# mainSchem.net
KiCad netlist of a schematic drawn in Altium Designer
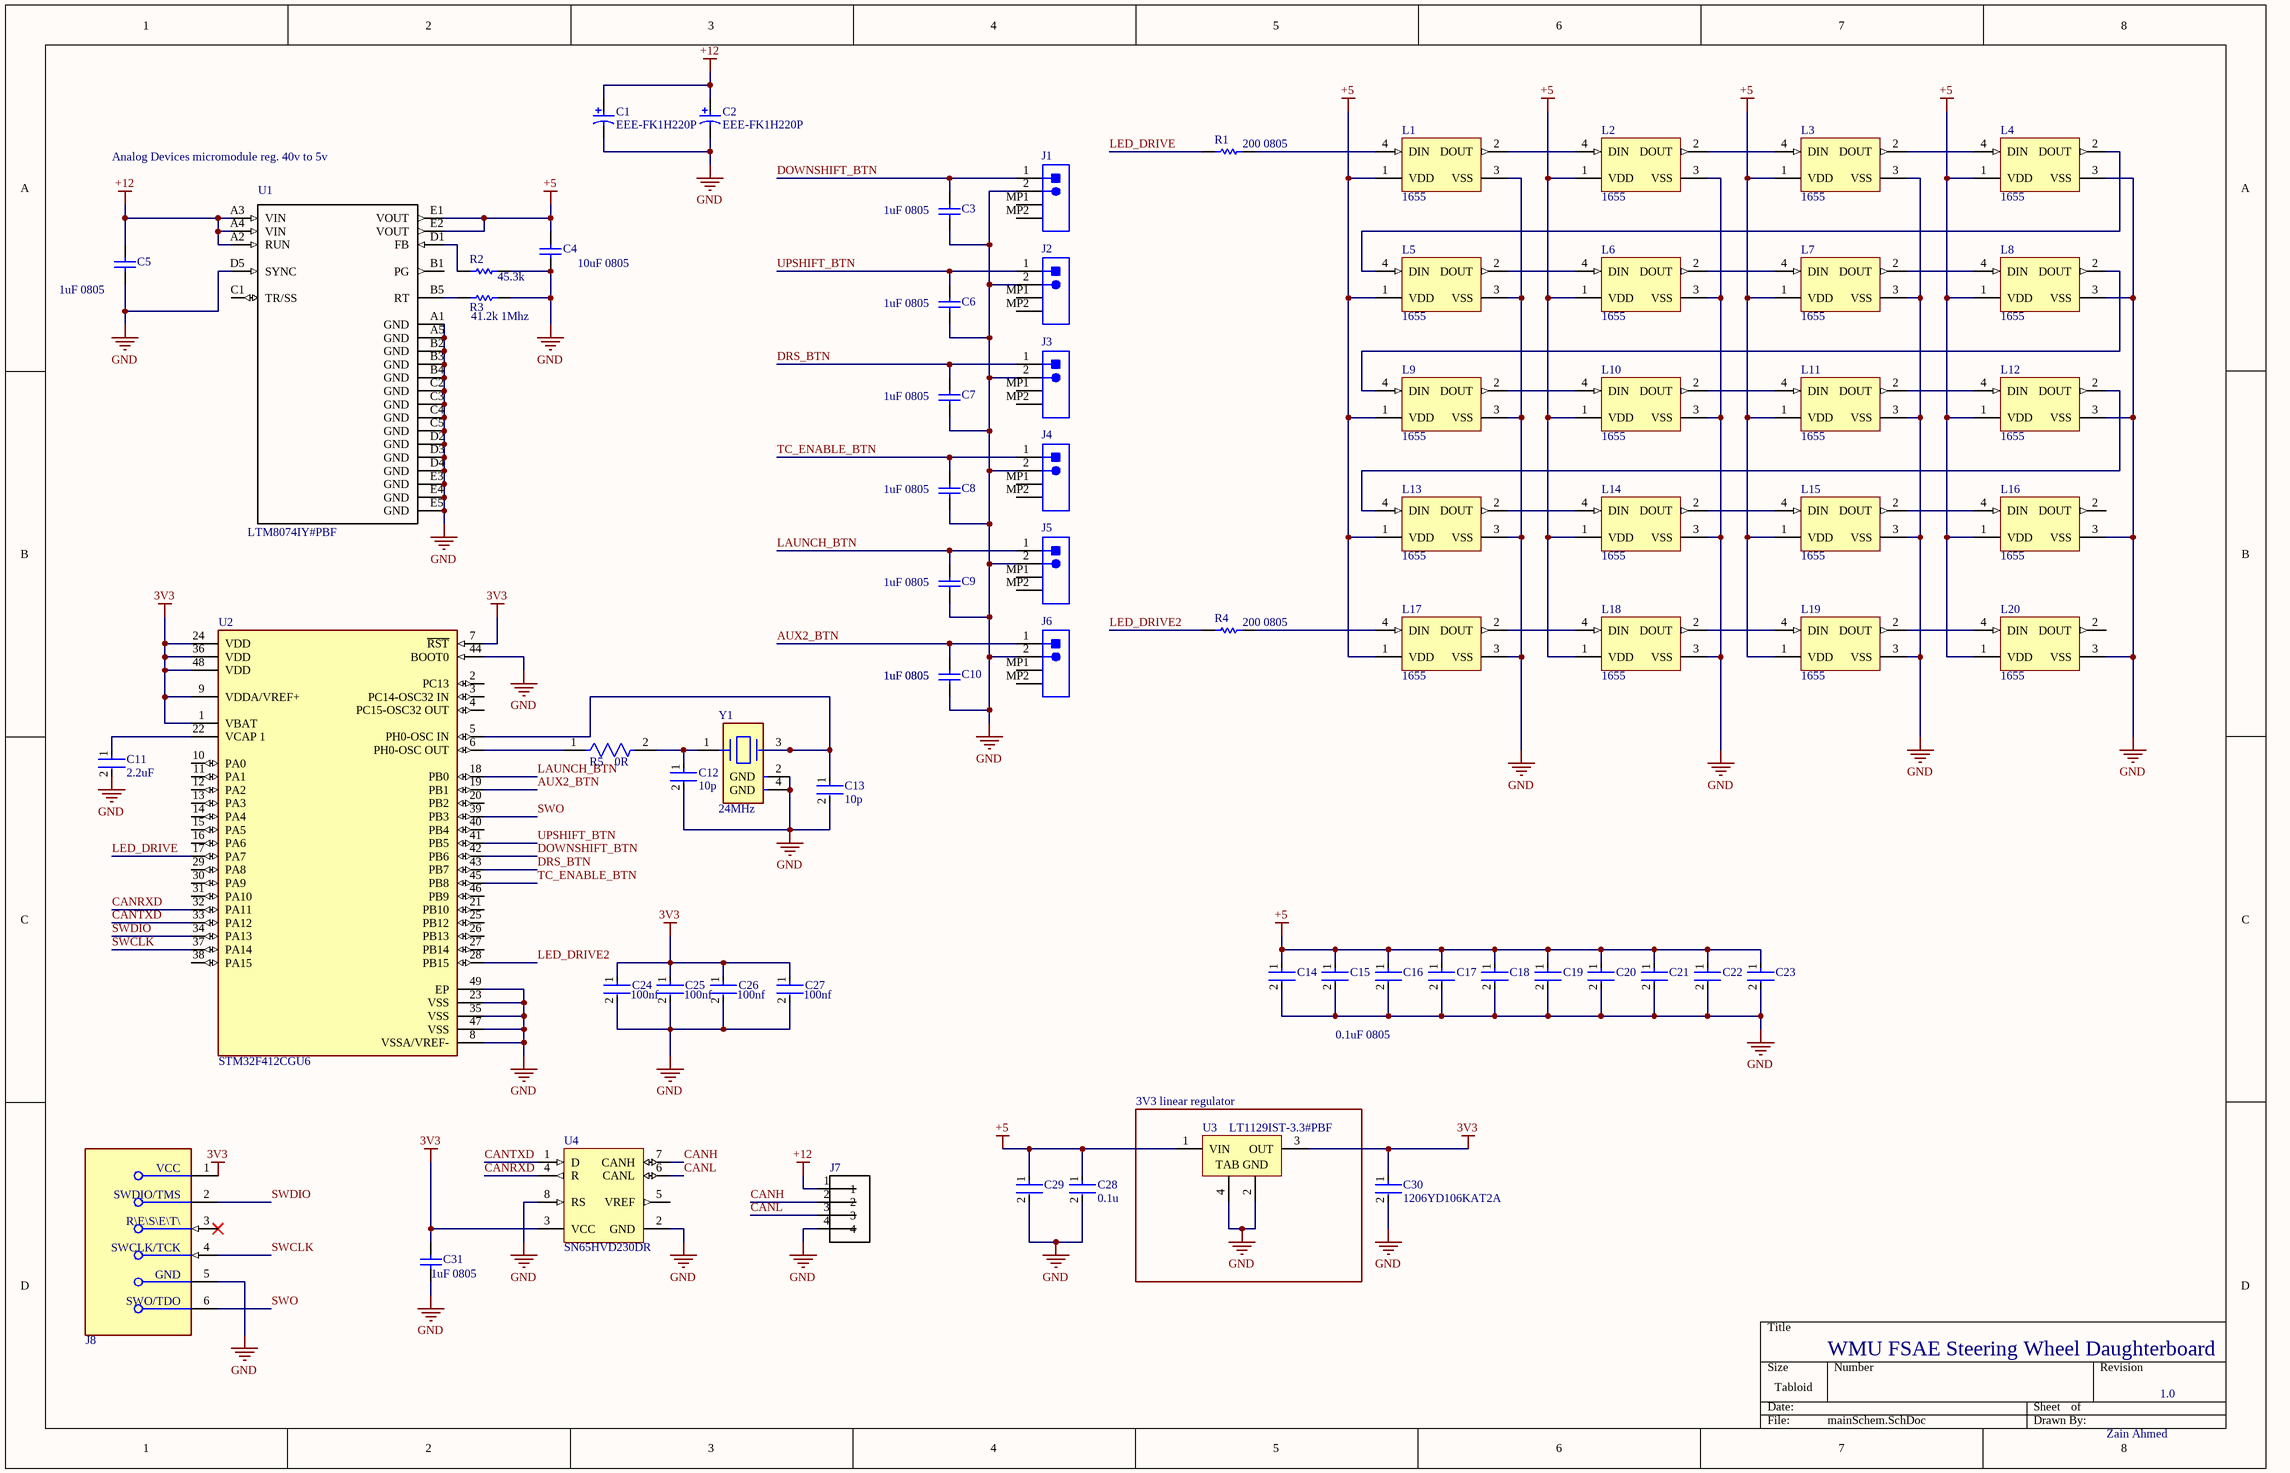
[diagram p0: mainSchem.SchDoc]

(export (version "E")
  (design (tool "Eeschema 10.0.6"))
  (components
    (comp (ref "C1")
      (value "EEE-FK1H220P")
      (footprint "PNSC-EEE-FK1H220P_L")
      (description "Cap Aluminum Lytic, 22 uF, +/- 20%, 6.3 to 100 V, -55 to 105 degC, 2-Pin SMD, RoHS, Tape and Reel")
      (fields (field (name "MANUFACTURER") "Panasonic"))
      (libsource (lib "Altium Content Vault") (part "CAP-P-2"))
    )
    (comp (ref "C2")
      (value "EEE-FK1H220P")
      (footprint "PNSC-EEE-FK1H220P_L")
      (description "Cap Aluminum Lytic, 22 uF, +/- 20%, 6.3 to 100 V, -55 to 105 degC, 2-Pin SMD, RoHS, Tape and Reel")
      (fields (field (name "MANUFACTURER") "Panasonic"))
      (libsource (lib "Altium Content Vault") (part "CAP-P-2"))
    )
    (comp (ref "C3")
      (value "GRM216R61E105KA12D")
      (footprint "CAPC2013X70X45NL10T25")
      (fields (field (name "MANUFACTURER") "Murata"))
      (libsource (lib "Altium Content Vault") (part "CAP"))
    )
    (comp (ref "C4")
      (value "GRM21BR61C106KE15L")
      (footprint "CAPC2013X135X50LL10T20")
      (fields (field (name "MANUFACTURER") "Murata"))
      (libsource (lib "Altium Content Vault") (part "CAP"))
    )
    (comp (ref "C5")
      (value "GRM216R61E105KA12D")
      (footprint "CAPC2013X70X45NL10T25")
      (fields (field (name "MANUFACTURER") "Murata"))
      (libsource (lib "Altium Content Vault") (part "CAP"))
    )
    (comp (ref "C6")
      (value "GRM216R61E105KA12D")
      (footprint "CAPC2013X70X45NL10T25")
      (fields (field (name "MANUFACTURER") "Murata"))
      (libsource (lib "Altium Content Vault") (part "CAP"))
    )
    (comp (ref "C7")
      (value "GRM216R61E105KA12D")
      (footprint "CAPC2013X70X45NL10T25")
      (fields (field (name "MANUFACTURER") "Murata"))
      (libsource (lib "Altium Content Vault") (part "CAP"))
    )
    (comp (ref "C8")
      (value "GRM216R61E105KA12D")
      (footprint "CAPC2013X70X45NL10T25")
      (fields (field (name "MANUFACTURER") "Murata"))
      (libsource (lib "Altium Content Vault") (part "CAP"))
    )
    (comp (ref "C9")
      (value "GRM216R61E105KA12D")
      (footprint "CAPC2013X70X45NL10T25")
      (fields (field (name "MANUFACTURER") "Murata"))
      (libsource (lib "Altium Content Vault") (part "CAP"))
    )
    (comp (ref "C10")
      (value "GRM216R61E105KA12D")
      (footprint "CAPC2013X70X45NL10T25")
      (fields (field (name "MANUFACTURER") "Murata"))
      (libsource (lib "Altium Content Vault") (part "CAP"))
    )
    (comp (ref "C11")
      (value "2.2uF")
      (footprint "FP-GRM188-0_1-e0_2_0_5-MFG")
      (description "Chip Multilayer Ceramic Capacitors for General Purpose, 0603, 2.2uF, X7R, 15%, 10%, 10V")
      (fields (field (name "VOLTAGE") "10V") (field (name "TOLERANCE") "10%"))
      (libsource (lib "Altium Content Vault") (part "11868f565c42a9108669ba33697ecf6"))
    )
    (comp (ref "C12")
      (value "10p")
      (footprint "FP-0603-L_1_6_0_15-W_0_81-IPC_C")
      (description "General Purpose Ceramic Capacitor, 0603, 10pF, 10%, NP0, 30ppm/°C, 50V")
      (fields (field (name "TOLERANCE") "10%") (field (name "VOLTAGE") "50V"))
      (libsource (lib "Altium Content Vault") (part "02cd4be3c70576c341d710602a673aa"))
    )
    (comp (ref "C13")
      (value "10p")
      (footprint "FP-0603-L_1_6_0_15-W_0_81-IPC_C")
      (description "General Purpose Ceramic Capacitor, 0603, 10pF, 10%, NP0, 30ppm/°C, 50V")
      (fields (field (name "TOLERANCE") "10%") (field (name "VOLTAGE") "50V"))
      (libsource (lib "Altium Content Vault") (part "02cd4be3c70576c341d710602a673aa"))
    )
    (comp (ref "C14")
      (value "C0805C104K5RACTU")
      (footprint "FP-C0805C-DN-MFG")
      (description "CAP CER 0.1UF 50V X7R 0805")
      (fields
        (field (name "MANUFACTURER") "KEMET")
        (field (name "OCTOPART") "https://octopart.com/c0805c104k5ractu-kemet-143926")
      )
      (libsource (lib "Altium Content Vault") (part "b4654b650e69147ec39a6b967a45e02"))
    )
    (comp (ref "C15")
      (value "C0805C104K5RACTU")
      (footprint "FP-C0805C-DN-MFG")
      (description "CAP CER 0.1UF 50V X7R 0805")
      (fields
        (field (name "MANUFACTURER") "KEMET")
        (field (name "OCTOPART") "https://octopart.com/c0805c104k5ractu-kemet-143926")
      )
      (libsource (lib "Altium Content Vault") (part "b4654b650e69147ec39a6b967a45e02"))
    )
    (comp (ref "C16")
      (value "C0805C104K5RACTU")
      (footprint "FP-C0805C-DN-MFG")
      (description "CAP CER 0.1UF 50V X7R 0805")
      (fields
        (field (name "MANUFACTURER") "KEMET")
        (field (name "OCTOPART") "https://octopart.com/c0805c104k5ractu-kemet-143926")
      )
      (libsource (lib "Altium Content Vault") (part "b4654b650e69147ec39a6b967a45e02"))
    )
    (comp (ref "C17")
      (value "C0805C104K5RACTU")
      (footprint "FP-C0805C-DN-MFG")
      (description "CAP CER 0.1UF 50V X7R 0805")
      (fields
        (field (name "MANUFACTURER") "KEMET")
        (field (name "OCTOPART") "https://octopart.com/c0805c104k5ractu-kemet-143926")
      )
      (libsource (lib "Altium Content Vault") (part "b4654b650e69147ec39a6b967a45e02"))
    )
    (comp (ref "C18")
      (value "C0805C104K5RACTU")
      (footprint "FP-C0805C-DN-MFG")
      (description "CAP CER 0.1UF 50V X7R 0805")
      (fields
        (field (name "MANUFACTURER") "KEMET")
        (field (name "OCTOPART") "https://octopart.com/c0805c104k5ractu-kemet-143926")
      )
      (libsource (lib "Altium Content Vault") (part "b4654b650e69147ec39a6b967a45e02"))
    )
    (comp (ref "C19")
      (value "C0805C104K5RACTU")
      (footprint "FP-C0805C-DN-MFG")
      (description "CAP CER 0.1UF 50V X7R 0805")
      (fields
        (field (name "MANUFACTURER") "KEMET")
        (field (name "OCTOPART") "https://octopart.com/c0805c104k5ractu-kemet-143926")
      )
      (libsource (lib "Altium Content Vault") (part "b4654b650e69147ec39a6b967a45e02"))
    )
    (comp (ref "C20")
      (value "C0805C104K5RACTU")
      (footprint "FP-C0805C-DN-MFG")
      (description "CAP CER 0.1UF 50V X7R 0805")
      (fields
        (field (name "MANUFACTURER") "KEMET")
        (field (name "OCTOPART") "https://octopart.com/c0805c104k5ractu-kemet-143926")
      )
      (libsource (lib "Altium Content Vault") (part "b4654b650e69147ec39a6b967a45e02"))
    )
    (comp (ref "C21")
      (value "C0805C104K5RACTU")
      (footprint "FP-C0805C-DN-MFG")
      (description "CAP CER 0.1UF 50V X7R 0805")
      (fields
        (field (name "MANUFACTURER") "KEMET")
        (field (name "OCTOPART") "https://octopart.com/c0805c104k5ractu-kemet-143926")
      )
      (libsource (lib "Altium Content Vault") (part "b4654b650e69147ec39a6b967a45e02"))
    )
    (comp (ref "C22")
      (value "C0805C104K5RACTU")
      (footprint "FP-C0805C-DN-MFG")
      (description "CAP CER 0.1UF 50V X7R 0805")
      (fields
        (field (name "MANUFACTURER") "KEMET")
        (field (name "OCTOPART") "https://octopart.com/c0805c104k5ractu-kemet-143926")
      )
      (libsource (lib "Altium Content Vault") (part "b4654b650e69147ec39a6b967a45e02"))
    )
    (comp (ref "C23")
      (value "C0805C104K5RACTU")
      (footprint "FP-C0805C-DN-MFG")
      (description "CAP CER 0.1UF 50V X7R 0805")
      (fields
        (field (name "MANUFACTURER") "KEMET")
        (field (name "OCTOPART") "https://octopart.com/c0805c104k5ractu-kemet-143926")
      )
      (libsource (lib "Altium Content Vault") (part "b4654b650e69147ec39a6b967a45e02"))
    )
    (comp (ref "C24")
      (value "C0402C104K8PACTU")
      (footprint "FP-C0402-BB-MFG")
      (description "CAP CER 0.1UF 10V X5R 0402")
      (fields (field (name "MANUFACTURER") "Kemet") (field (name "TOLERANCE") "0.1"))
      (libsource (lib "Altium Content Vault") (part "b4654b650e69147ec39a6b967a45e02"))
    )
    (comp (ref "C25")
      (value "C0402C104K8PACTU")
      (footprint "FP-C0402-BB-MFG")
      (description "CAP CER 0.1UF 10V X5R 0402")
      (fields (field (name "MANUFACTURER") "Kemet") (field (name "TOLERANCE") "0.1"))
      (libsource (lib "Altium Content Vault") (part "b4654b650e69147ec39a6b967a45e02"))
    )
    (comp (ref "C26")
      (value "C0402C104K8PACTU")
      (footprint "FP-C0402-BB-MFG")
      (description "CAP CER 0.1UF 10V X5R 0402")
      (fields (field (name "MANUFACTURER") "Kemet") (field (name "TOLERANCE") "0.1"))
      (libsource (lib "Altium Content Vault") (part "b4654b650e69147ec39a6b967a45e02"))
    )
    (comp (ref "C27")
      (value "C0402C104K8PACTU")
      (footprint "FP-C0402-BB-MFG")
      (description "CAP CER 0.1UF 10V X5R 0402")
      (fields (field (name "MANUFACTURER") "Kemet") (field (name "TOLERANCE") "0.1"))
      (libsource (lib "Altium Content Vault") (part "b4654b650e69147ec39a6b967a45e02"))
    )
    (comp (ref "C28")
      (value "0.1u")
      (footprint "FP-C0603C-CF-MFG")
      (description "CAP CER 0.1UF 50V X7R 0603")
      (fields (field (name "TOLERANCE") "0.1") (field (name "MANUFACTURER") "KEMET"))
      (libsource (lib "Altium Content Vault") (part "b4654b650e69147ec39a6b967a45e02"))
    )
    (comp (ref "C29")
      (value "1206YD106KAT2A")
      (footprint "FP-1206-L_3_2_0_2-W_1_6_0-IPC_B")
      (description "General Purpose Ceramic Capacitor, 1206, 10uF, 10%, X5R, 15%, 16V")
      (fields (field (name "TOLERANCE") "10%") (field (name "VOLTAGE") "16V"))
      (libsource (lib "Altium Content Vault") (part "02cd4be3c70576c341d710602a673aa"))
    )
    (comp (ref "C30")
      (value "1206YD106KAT2A")
      (footprint "FP-1206-L_3_2_0_2-W_1_6_0-IPC_B")
      (description "General Purpose Ceramic Capacitor, 1206, 10uF, 10%, X5R, 15%, 16V")
      (fields (field (name "TOLERANCE") "10%") (field (name "VOLTAGE") "16V"))
      (libsource (lib "Altium Content Vault") (part "02cd4be3c70576c341d710602a673aa"))
    )
    (comp (ref "C31")
      (value "GRM216R61E105KA12D")
      (footprint "CAPC2013X70X45NL10T25")
      (fields (field (name "MANUFACTURER") "Murata"))
      (libsource (lib "Altium Content Vault") (part "CAP"))
    )
    (comp (ref "J1")
      (value "B2B-PH-SM4-TB(LF)(SN)")
      (footprint "JST-B2B-PH-SM4-TB-2_V")
      (description "Male Header, Pitch 2 mm, 1 x 2 Position, Height 6.6 mm, RoHS, Tape and Reel")
      (fields (field (name "MANUFACTURER") "JST"))
      (libsource (lib "Altium Content Vault") (part "CN-1P-2M-R2"))
    )
    (comp (ref "J2")
      (value "B2B-PH-SM4-TB(LF)(SN)")
      (footprint "JST-B2B-PH-SM4-TB-2_V")
      (description "Male Header, Pitch 2 mm, 1 x 2 Position, Height 6.6 mm, RoHS, Tape and Reel")
      (fields (field (name "MANUFACTURER") "JST"))
      (libsource (lib "Altium Content Vault") (part "CN-1P-2M-R2"))
    )
    (comp (ref "J3")
      (value "B2B-PH-SM4-TB(LF)(SN)")
      (footprint "JST-B2B-PH-SM4-TB-2_V")
      (description "Male Header, Pitch 2 mm, 1 x 2 Position, Height 6.6 mm, RoHS, Tape and Reel")
      (fields (field (name "MANUFACTURER") "JST"))
      (libsource (lib "Altium Content Vault") (part "CN-1P-2M-R2"))
    )
    (comp (ref "J4")
      (value "B2B-PH-SM4-TB(LF)(SN)")
      (footprint "JST-B2B-PH-SM4-TB-2_V")
      (description "Male Header, Pitch 2 mm, 1 x 2 Position, Height 6.6 mm, RoHS, Tape and Reel")
      (fields (field (name "MANUFACTURER") "JST"))
      (libsource (lib "Altium Content Vault") (part "CN-1P-2M-R2"))
    )
    (comp (ref "J5")
      (value "B2B-PH-SM4-TB(LF)(SN)")
      (footprint "JST-B2B-PH-SM4-TB-2_V")
      (description "Male Header, Pitch 2 mm, 1 x 2 Position, Height 6.6 mm, RoHS, Tape and Reel")
      (fields (field (name "MANUFACTURER") "JST"))
      (libsource (lib "Altium Content Vault") (part "CN-1P-2M-R2"))
    )
    (comp (ref "J6")
      (value "B2B-PH-SM4-TB(LF)(SN)")
      (footprint "JST-B2B-PH-SM4-TB-2_V")
      (description "Male Header, Pitch 2 mm, 1 x 2 Position, Height 6.6 mm, RoHS, Tape and Reel")
      (fields (field (name "MANUFACTURER") "JST"))
      (libsource (lib "Altium Content Vault") (part "CN-1P-2M-R2"))
    )
    (comp (ref "J7")
      (value "B4B-PH-SM4-TB")
      (footprint "*JST_B4B-PH-SM4-TB")
      (description "Connector Header Surface Mount 4 position 0.079 _2.00mm_")
      (fields (field (name "MF") "JST Sales"))
      (libsource (lib "B4B-PH-SM4-TB") (part "B4B-PH-SM4-TB"))
    )
    (comp (ref "J8")
      (value "TC2030-CTX-NL")
      (footprint "Tag_Connect_0_MFG")
      (libsource (lib "Conn_Tag_Connect_TC2030-CTX-NL_eec") (part "TC2030-CTX-NL"))
    )
    (comp (ref "L1")
      (value "1655")
      (footprint "ADA-RGB-1655_V")
      (fields (field (name "MANUFACTURER") "Adafruit-Industries-LLC"))
      (libsource (lib "Altium Content Vault") (part "ADA-RGB-1655-4"))
    )
    (comp (ref "L2")
      (value "1655")
      (footprint "ADA-RGB-1655_V")
      (fields (field (name "MANUFACTURER") "Adafruit-Industries-LLC"))
      (libsource (lib "Altium Content Vault") (part "ADA-RGB-1655-4"))
    )
    (comp (ref "L3")
      (value "1655")
      (footprint "ADA-RGB-1655_V")
      (fields (field (name "MANUFACTURER") "Adafruit-Industries-LLC"))
      (libsource (lib "Altium Content Vault") (part "ADA-RGB-1655-4"))
    )
    (comp (ref "L4")
      (value "1655")
      (footprint "ADA-RGB-1655_V")
      (fields (field (name "MANUFACTURER") "Adafruit-Industries-LLC"))
      (libsource (lib "Altium Content Vault") (part "ADA-RGB-1655-4"))
    )
    (comp (ref "L5")
      (value "1655")
      (footprint "ADA-RGB-1655_V")
      (fields (field (name "MANUFACTURER") "Adafruit-Industries-LLC"))
      (libsource (lib "Altium Content Vault") (part "ADA-RGB-1655-4"))
    )
    (comp (ref "L6")
      (value "1655")
      (footprint "ADA-RGB-1655_V")
      (fields (field (name "MANUFACTURER") "Adafruit-Industries-LLC"))
      (libsource (lib "Altium Content Vault") (part "ADA-RGB-1655-4"))
    )
    (comp (ref "L7")
      (value "1655")
      (footprint "ADA-RGB-1655_V")
      (fields (field (name "MANUFACTURER") "Adafruit-Industries-LLC"))
      (libsource (lib "Altium Content Vault") (part "ADA-RGB-1655-4"))
    )
    (comp (ref "L8")
      (value "1655")
      (footprint "ADA-RGB-1655_V")
      (fields (field (name "MANUFACTURER") "Adafruit-Industries-LLC"))
      (libsource (lib "Altium Content Vault") (part "ADA-RGB-1655-4"))
    )
    (comp (ref "L9")
      (value "1655")
      (footprint "ADA-RGB-1655_V")
      (fields (field (name "MANUFACTURER") "Adafruit-Industries-LLC"))
      (libsource (lib "Altium Content Vault") (part "ADA-RGB-1655-4"))
    )
    (comp (ref "L10")
      (value "1655")
      (footprint "ADA-RGB-1655_V")
      (fields (field (name "MANUFACTURER") "Adafruit-Industries-LLC"))
      (libsource (lib "Altium Content Vault") (part "ADA-RGB-1655-4"))
    )
    (comp (ref "L11")
      (value "1655")
      (footprint "ADA-RGB-1655_V")
      (fields (field (name "MANUFACTURER") "Adafruit-Industries-LLC"))
      (libsource (lib "Altium Content Vault") (part "ADA-RGB-1655-4"))
    )
    (comp (ref "L12")
      (value "1655")
      (footprint "ADA-RGB-1655_V")
      (fields (field (name "MANUFACTURER") "Adafruit-Industries-LLC"))
      (libsource (lib "Altium Content Vault") (part "ADA-RGB-1655-4"))
    )
    (comp (ref "L13")
      (value "1655")
      (footprint "ADA-RGB-1655_V")
      (fields (field (name "MANUFACTURER") "Adafruit-Industries-LLC"))
      (libsource (lib "Altium Content Vault") (part "ADA-RGB-1655-4"))
    )
    (comp (ref "L14")
      (value "1655")
      (footprint "ADA-RGB-1655_V")
      (fields (field (name "MANUFACTURER") "Adafruit-Industries-LLC"))
      (libsource (lib "Altium Content Vault") (part "ADA-RGB-1655-4"))
    )
    (comp (ref "L15")
      (value "1655")
      (footprint "ADA-RGB-1655_V")
      (fields (field (name "MANUFACTURER") "Adafruit-Industries-LLC"))
      (libsource (lib "Altium Content Vault") (part "ADA-RGB-1655-4"))
    )
    (comp (ref "L16")
      (value "1655")
      (footprint "ADA-RGB-1655_V")
      (fields (field (name "MANUFACTURER") "Adafruit-Industries-LLC"))
      (libsource (lib "Altium Content Vault") (part "ADA-RGB-1655-4"))
    )
    (comp (ref "L17")
      (value "1655")
      (footprint "ADA-RGB-1655_V")
      (fields (field (name "MANUFACTURER") "Adafruit-Industries-LLC"))
      (libsource (lib "Altium Content Vault") (part "ADA-RGB-1655-4"))
    )
    (comp (ref "L18")
      (value "1655")
      (footprint "ADA-RGB-1655_V")
      (fields (field (name "MANUFACTURER") "Adafruit-Industries-LLC"))
      (libsource (lib "Altium Content Vault") (part "ADA-RGB-1655-4"))
    )
    (comp (ref "L19")
      (value "1655")
      (footprint "ADA-RGB-1655_V")
      (fields (field (name "MANUFACTURER") "Adafruit-Industries-LLC"))
      (libsource (lib "Altium Content Vault") (part "ADA-RGB-1655-4"))
    )
    (comp (ref "L20")
      (value "1655")
      (footprint "ADA-RGB-1655_V")
      (fields (field (name "MANUFACTURER") "Adafruit-Industries-LLC"))
      (libsource (lib "Altium Content Vault") (part "ADA-RGB-1655-4"))
    )
    (comp (ref "R1")
      (value "ERA6AEB201V")
      (footprint "RESC2013X60X40NL20T25")
      (fields (field (name "MANUFACTURER") "Panasonic"))
      (libsource (lib "Altium Content Vault") (part "RES"))
    )
    (comp (ref "R2")
      (value "ERJ-6ENF4532V")
      (footprint "RESC2013X70X40ML20T20")
      (fields (field (name "MANUFACTURER") "Panasonic"))
      (libsource (lib "Altium Content Vault") (part "RES"))
    )
    (comp (ref "R3")
      (value "ERJ-6ENF4122V")
      (footprint "RESC2013X70X40LL20T20")
      (fields (field (name "MANUFACTURER") "Panasonic"))
      (libsource (lib "Altium Content Vault") (part "RES"))
    )
    (comp (ref "R4")
      (value "ERA6AEB201V")
      (footprint "RESC2013X60X40NL20T25")
      (fields (field (name "MANUFACTURER") "Panasonic"))
      (libsource (lib "Altium Content Vault") (part "RES"))
    )
    (comp (ref "R5")
      (value "0R")
      (footprint "FP-RC0603-MFG")
      (description "RES SMD 0 OHM JUMPER 1/10W 0603")
      (fields
        (field (name "TOLERANCE") "1%")
        (field (name "OCTOPART") "https://octopart.com/rc0603fr-070rl-yageo-1180803")
      )
      (libsource (lib "Altium Content Vault") (part "1029c3af85768c4190bb7ad29bc67b5"))
    )
    (comp (ref "U1")
      (value "LTM8074IY#PBF")
      (footprint "*BGA25C65P5X5_400X400X198N_LTM8074IY#PBF(Primary)")
      (description "40Vin, 0.7A Step Dwn uModule Reg")
      (fields (field (name "MF") "Analog Devices"))
      (libsource (lib "LTM8074IY_PBF") (part "LTM8074IY#PBF"))
    )
    (comp (ref "U2")
      (value "STM32F412CGU6")
      (footprint "FP-UFQFPN48-A0B9-MFG")
      (description "IC MCU 32BIT 1MB FLASH 48UFQFPN")
      (libsource (lib "Altium Content Vault") (part "7dd92b861eb4b166e7106aa1111722c"))
    )
    (comp (ref "U3")
      (value "LT1129IST-3.3#PBF")
      (footprint "LT-ST-3-SOT-223_L")
      (fields (field (name "MANUFACTURER") "Linear Technology"))
      (libsource (lib "Altium Content Vault") (part "LT-LT112X-ST-3"))
    )
    (comp (ref "U4")
      (value "SN65HVD230DR")
      (footprint "D0008A_L")
      (fields (field (name "MANUFACTURER") "Texas Instruments"))
      (libsource (lib "Altium Content Vault") (part "TI-SN65HVD230-SOIC_D-8"))
    )
    (comp (ref "Y1")
      (value "24MHz")
      (footprint "FP-7M-MFG")
      (description "Crystal 24MHz, 10ppm, 10pF, 50Ω")
      (fields (field (name "TOLERANCE") "10ppm"))
      (libsource (lib "Altium Content Vault") (part "41079aabb0e87794b56622915be14ed"))
    )
  )
  (nets
    (net (code "1") (name "+5") (class "Default")
      (node (ref "C14") (pin "1") (pinfunction "1_1") (pintype "passive"))
      (node (ref "C15") (pin "1") (pinfunction "1_1") (pintype "passive"))
      (node (ref "C16") (pin "1") (pinfunction "1_1") (pintype "passive"))
      (node (ref "C17") (pin "1") (pinfunction "1_1") (pintype "passive"))
      (node (ref "C18") (pin "1") (pinfunction "1_1") (pintype "passive"))
      (node (ref "C19") (pin "1") (pinfunction "1_1") (pintype "passive"))
      (node (ref "C20") (pin "1") (pinfunction "1_1") (pintype "passive"))
      (node (ref "C21") (pin "1") (pinfunction "1_1") (pintype "passive"))
      (node (ref "C22") (pin "1") (pinfunction "1_1") (pintype "passive"))
      (node (ref "C23") (pin "1") (pinfunction "1_1") (pintype "passive"))
      (node (ref "C28") (pin "1") (pinfunction "1_1") (pintype "passive"))
      (node (ref "C29") (pin "1") (pinfunction "1_1") (pintype "passive"))
      (node (ref "C4") (pin "1") (pinfunction "1_1") (pintype "passive"))
      (node (ref "L1") (pin "1") (pinfunction "VDD_1") (pintype "power_in"))
      (node (ref "L10") (pin "1") (pinfunction "VDD_1") (pintype "power_in"))
      (node (ref "L11") (pin "1") (pinfunction "VDD_1") (pintype "power_in"))
      (node (ref "L12") (pin "1") (pinfunction "VDD_1") (pintype "power_in"))
      (node (ref "L13") (pin "1") (pinfunction "VDD_1") (pintype "power_in"))
      (node (ref "L14") (pin "1") (pinfunction "VDD_1") (pintype "power_in"))
      (node (ref "L15") (pin "1") (pinfunction "VDD_1") (pintype "power_in"))
      (node (ref "L16") (pin "1") (pinfunction "VDD_1") (pintype "power_in"))
      (node (ref "L17") (pin "1") (pinfunction "VDD_1") (pintype "power_in"))
      (node (ref "L18") (pin "1") (pinfunction "VDD_1") (pintype "power_in"))
      (node (ref "L19") (pin "1") (pinfunction "VDD_1") (pintype "power_in"))
      (node (ref "L2") (pin "1") (pinfunction "VDD_1") (pintype "power_in"))
      (node (ref "L20") (pin "1") (pinfunction "VDD_1") (pintype "power_in"))
      (node (ref "L3") (pin "1") (pinfunction "VDD_1") (pintype "power_in"))
      (node (ref "L4") (pin "1") (pinfunction "VDD_1") (pintype "power_in"))
      (node (ref "L5") (pin "1") (pinfunction "VDD_1") (pintype "power_in"))
      (node (ref "L6") (pin "1") (pinfunction "VDD_1") (pintype "power_in"))
      (node (ref "L7") (pin "1") (pinfunction "VDD_1") (pintype "power_in"))
      (node (ref "L8") (pin "1") (pinfunction "VDD_1") (pintype "power_in"))
      (node (ref "L9") (pin "1") (pinfunction "VDD_1") (pintype "power_in"))
      (node (ref "U1") (pin "E1") (pinfunction "VOUT_E1") (pintype "output"))
      (node (ref "U1") (pin "E2") (pinfunction "VOUT_E2") (pintype "output"))
      (node (ref "U3") (pin "1") (pinfunction "VIN_1") (pintype "power_in"))
    )
    (net (code "2") (name "+12") (class "Default")
      (node (ref "C1") (pin "1") (pinfunction "1_1") (pintype "passive"))
      (node (ref "C2") (pin "1") (pinfunction "1_1") (pintype "passive"))
      (node (ref "C5") (pin "1") (pinfunction "1_1") (pintype "passive"))
      (node (ref "J7") (pin "1") (pinfunction "1_1") (pintype "passive"))
      (node (ref "U1") (pin "A2") (pinfunction "RUN_A2") (pintype "input"))
      (node (ref "U1") (pin "A3") (pinfunction "VIN_A3") (pintype "input"))
      (node (ref "U1") (pin "A4") (pinfunction "VIN_A4") (pintype "input"))
    )
    (net (code "3") (name "/AUX2_BTN") (class "Default")
      (node (ref "C10") (pin "1") (pinfunction "1_1") (pintype "passive"))
      (node (ref "J6") (pin "1") (pinfunction "1_1") (pintype "passive"))
      (node (ref "U2") (pin "19") (pinfunction "PB1_19") (pintype "bidirectional"))
    )
    (net (code "4") (name "/CANH") (class "Default")
      (node (ref "J7") (pin "2") (pinfunction "2_2") (pintype "passive"))
      (node (ref "U4") (pin "7") (pinfunction "CANH_7") (pintype "bidirectional"))
    )
    (net (code "5") (name "/CANL") (class "Default")
      (node (ref "J7") (pin "3") (pinfunction "3_3") (pintype "passive"))
      (node (ref "U4") (pin "6") (pinfunction "CANL_6") (pintype "bidirectional"))
    )
    (net (code "6") (name "/CANRXD") (class "Default")
      (node (ref "U2") (pin "32") (pinfunction "PA11_32") (pintype "bidirectional"))
      (node (ref "U4") (pin "4") (pinfunction "R_4") (pintype "output"))
    )
    (net (code "7") (name "/CANTXD") (class "Default")
      (node (ref "U2") (pin "33") (pinfunction "PA12_33") (pintype "bidirectional"))
      (node (ref "U4") (pin "1") (pinfunction "D_1") (pintype "input"))
    )
    (net (code "8") (name "/DOWNSHIFT_BTN") (class "Default")
      (node (ref "C3") (pin "1") (pinfunction "1_1") (pintype "passive"))
      (node (ref "J1") (pin "1") (pinfunction "1_1") (pintype "passive"))
      (node (ref "U2") (pin "42") (pinfunction "PB6_42") (pintype "bidirectional"))
    )
    (net (code "9") (name "/DRS_BTN") (class "Default")
      (node (ref "C7") (pin "1") (pinfunction "1_1") (pintype "passive"))
      (node (ref "J3") (pin "1") (pinfunction "1_1") (pintype "passive"))
      (node (ref "U2") (pin "43") (pinfunction "PB7_43") (pintype "bidirectional"))
    )
    (net (code "10") (name "/LAUNCH_BTN") (class "Default")
      (node (ref "C9") (pin "1") (pinfunction "1_1") (pintype "passive"))
      (node (ref "J5") (pin "1") (pinfunction "1_1") (pintype "passive"))
      (node (ref "U2") (pin "18") (pinfunction "PB0_18") (pintype "bidirectional"))
    )
    (net (code "11") (name "/LED_DRIVE") (class "Default")
      (node (ref "R1") (pin "1") (pinfunction "1_1") (pintype "passive"))
      (node (ref "U2") (pin "17") (pinfunction "PA7_17") (pintype "bidirectional"))
    )
    (net (code "12") (name "/LED_DRIVE2") (class "Default")
      (node (ref "R4") (pin "1") (pinfunction "1_1") (pintype "passive"))
      (node (ref "U2") (pin "28") (pinfunction "PB15_28") (pintype "bidirectional"))
    )
    (net (code "13") (name "/SWCLK") (class "Default")
      (node (ref "J8") (pin "4") (pinfunction "SWCLK/TCK_4") (pintype "input"))
      (node (ref "U2") (pin "37") (pinfunction "PA14_37") (pintype "bidirectional"))
    )
    (net (code "14") (name "/SWDIO") (class "Default")
      (node (ref "J8") (pin "2") (pinfunction "SWDIO/TMS_2") (pintype "passive"))
      (node (ref "U2") (pin "34") (pinfunction "PA13_34") (pintype "bidirectional"))
    )
    (net (code "15") (name "/SWO") (class "Default")
      (node (ref "J8") (pin "6") (pinfunction "SWO/TDO_6") (pintype "passive"))
      (node (ref "U2") (pin "39") (pinfunction "PB3_39") (pintype "bidirectional"))
    )
    (net (code "16") (name "/TC_ENABLE_BTN") (class "Default")
      (node (ref "C8") (pin "1") (pinfunction "1_1") (pintype "passive"))
      (node (ref "J4") (pin "1") (pinfunction "1_1") (pintype "passive"))
      (node (ref "U2") (pin "45") (pinfunction "PB8_45") (pintype "bidirectional"))
    )
    (net (code "17") (name "/UPSHIFT_BTN") (class "Default")
      (node (ref "C6") (pin "1") (pinfunction "1_1") (pintype "passive"))
      (node (ref "J2") (pin "1") (pinfunction "1_1") (pintype "passive"))
      (node (ref "U2") (pin "41") (pinfunction "PB5_41") (pintype "bidirectional"))
    )
    (net (code "18") (name "3V3") (class "Default")
      (node (ref "C24") (pin "1") (pinfunction "1_1") (pintype "passive"))
      (node (ref "C25") (pin "1") (pinfunction "1_1") (pintype "passive"))
      (node (ref "C26") (pin "1") (pinfunction "1_1") (pintype "passive"))
      (node (ref "C27") (pin "1") (pinfunction "1_1") (pintype "passive"))
      (node (ref "C30") (pin "1") (pinfunction "1_1") (pintype "passive"))
      (node (ref "C31") (pin "1") (pinfunction "1_1") (pintype "passive"))
      (node (ref "J8") (pin "1") (pinfunction "VCC_1") (pintype "power_in"))
      (node (ref "U2") (pin "1") (pinfunction "VBAT_1") (pintype "power_in"))
      (node (ref "U2") (pin "24") (pinfunction "VDD_24") (pintype "power_in"))
      (node (ref "U2") (pin "36") (pinfunction "VDD_36") (pintype "power_in"))
      (node (ref "U2") (pin "48") (pinfunction "VDD_48") (pintype "power_in"))
      (node (ref "U2") (pin "7") (pinfunction "~{RST}_7") (pintype "input"))
      (node (ref "U2") (pin "9") (pinfunction "VDDA/VREF+_9") (pintype "power_in"))
      (node (ref "U3") (pin "3") (pinfunction "OUT_3") (pintype "power_in"))
      (node (ref "U4") (pin "3") (pinfunction "VCC_3") (pintype "power_in"))
    )
    (net (code "19") (name "GND") (class "Default")
      (node (ref "C1") (pin "2") (pinfunction "2_2") (pintype "passive"))
      (node (ref "C10") (pin "2") (pinfunction "2_2") (pintype "passive"))
      (node (ref "C11") (pin "2") (pinfunction "2_2") (pintype "passive"))
      (node (ref "C12") (pin "2") (pinfunction "2_2") (pintype "passive"))
      (node (ref "C13") (pin "2") (pinfunction "2_2") (pintype "passive"))
      (node (ref "C14") (pin "2") (pinfunction "2_2") (pintype "passive"))
      (node (ref "C15") (pin "2") (pinfunction "2_2") (pintype "passive"))
      (node (ref "C16") (pin "2") (pinfunction "2_2") (pintype "passive"))
      (node (ref "C17") (pin "2") (pinfunction "2_2") (pintype "passive"))
      (node (ref "C18") (pin "2") (pinfunction "2_2") (pintype "passive"))
      (node (ref "C19") (pin "2") (pinfunction "2_2") (pintype "passive"))
      (node (ref "C2") (pin "2") (pinfunction "2_2") (pintype "passive"))
      (node (ref "C20") (pin "2") (pinfunction "2_2") (pintype "passive"))
      (node (ref "C21") (pin "2") (pinfunction "2_2") (pintype "passive"))
      (node (ref "C22") (pin "2") (pinfunction "2_2") (pintype "passive"))
      (node (ref "C23") (pin "2") (pinfunction "2_2") (pintype "passive"))
      (node (ref "C24") (pin "2") (pinfunction "2_2") (pintype "passive"))
      (node (ref "C25") (pin "2") (pinfunction "2_2") (pintype "passive"))
      (node (ref "C26") (pin "2") (pinfunction "2_2") (pintype "passive"))
      (node (ref "C27") (pin "2") (pinfunction "2_2") (pintype "passive"))
      (node (ref "C28") (pin "2") (pinfunction "2_2") (pintype "passive"))
      (node (ref "C29") (pin "2") (pinfunction "2_2") (pintype "passive"))
      (node (ref "C3") (pin "2") (pinfunction "2_2") (pintype "passive"))
      (node (ref "C30") (pin "2") (pinfunction "2_2") (pintype "passive"))
      (node (ref "C31") (pin "2") (pinfunction "2_2") (pintype "passive"))
      (node (ref "C4") (pin "2") (pinfunction "2_2") (pintype "passive"))
      (node (ref "C5") (pin "2") (pinfunction "2_2") (pintype "passive"))
      (node (ref "C6") (pin "2") (pinfunction "2_2") (pintype "passive"))
      (node (ref "C7") (pin "2") (pinfunction "2_2") (pintype "passive"))
      (node (ref "C8") (pin "2") (pinfunction "2_2") (pintype "passive"))
      (node (ref "C9") (pin "2") (pinfunction "2_2") (pintype "passive"))
      (node (ref "J1") (pin "2") (pinfunction "2_2") (pintype "passive"))
      (node (ref "J2") (pin "2") (pinfunction "2_2") (pintype "passive"))
      (node (ref "J3") (pin "2") (pinfunction "2_2") (pintype "passive"))
      (node (ref "J4") (pin "2") (pinfunction "2_2") (pintype "passive"))
      (node (ref "J5") (pin "2") (pinfunction "2_2") (pintype "passive"))
      (node (ref "J6") (pin "2") (pinfunction "2_2") (pintype "passive"))
      (node (ref "J7") (pin "4") (pinfunction "4_4") (pintype "passive"))
      (node (ref "J8") (pin "5") (pinfunction "GND_5") (pintype "power_in"))
      (node (ref "L1") (pin "3") (pinfunction "VSS_3") (pintype "power_in"))
      (node (ref "L10") (pin "3") (pinfunction "VSS_3") (pintype "power_in"))
      (node (ref "L11") (pin "3") (pinfunction "VSS_3") (pintype "power_in"))
      (node (ref "L12") (pin "3") (pinfunction "VSS_3") (pintype "power_in"))
      (node (ref "L13") (pin "3") (pinfunction "VSS_3") (pintype "power_in"))
      (node (ref "L14") (pin "3") (pinfunction "VSS_3") (pintype "power_in"))
      (node (ref "L15") (pin "3") (pinfunction "VSS_3") (pintype "power_in"))
      (node (ref "L16") (pin "3") (pinfunction "VSS_3") (pintype "power_in"))
      (node (ref "L17") (pin "3") (pinfunction "VSS_3") (pintype "power_in"))
      (node (ref "L18") (pin "3") (pinfunction "VSS_3") (pintype "power_in"))
      (node (ref "L19") (pin "3") (pinfunction "VSS_3") (pintype "power_in"))
      (node (ref "L2") (pin "3") (pinfunction "VSS_3") (pintype "power_in"))
      (node (ref "L20") (pin "3") (pinfunction "VSS_3") (pintype "power_in"))
      (node (ref "L3") (pin "3") (pinfunction "VSS_3") (pintype "power_in"))
      (node (ref "L4") (pin "3") (pinfunction "VSS_3") (pintype "power_in"))
      (node (ref "L5") (pin "3") (pinfunction "VSS_3") (pintype "power_in"))
      (node (ref "L6") (pin "3") (pinfunction "VSS_3") (pintype "power_in"))
      (node (ref "L7") (pin "3") (pinfunction "VSS_3") (pintype "power_in"))
      (node (ref "L8") (pin "3") (pinfunction "VSS_3") (pintype "power_in"))
      (node (ref "L9") (pin "3") (pinfunction "VSS_3") (pintype "power_in"))
      (node (ref "R2") (pin "2") (pinfunction "2_2") (pintype "passive"))
      (node (ref "R3") (pin "2") (pinfunction "2_2") (pintype "passive"))
      (node (ref "U1") (pin "A1") (pinfunction "GND_A1") (pintype "power_in"))
      (node (ref "U1") (pin "A5") (pinfunction "GND_A5") (pintype "power_in"))
      (node (ref "U1") (pin "B2") (pinfunction "GND_B2") (pintype "power_in"))
      (node (ref "U1") (pin "B3") (pinfunction "GND_B3") (pintype "power_in"))
      (node (ref "U1") (pin "B4") (pinfunction "GND_B4") (pintype "power_in"))
      (node (ref "U1") (pin "C2") (pinfunction "GND_C2") (pintype "power_in"))
      (node (ref "U1") (pin "C3") (pinfunction "GND_C3") (pintype "power_in"))
      (node (ref "U1") (pin "C4") (pinfunction "GND_C4") (pintype "power_in"))
      (node (ref "U1") (pin "C5") (pinfunction "GND_C5") (pintype "power_in"))
      (node (ref "U1") (pin "D2") (pinfunction "GND_D2") (pintype "power_in"))
      (node (ref "U1") (pin "D3") (pinfunction "GND_D3") (pintype "power_in"))
      (node (ref "U1") (pin "D4") (pinfunction "GND_D4") (pintype "power_in"))
      (node (ref "U1") (pin "D5") (pinfunction "SYNC_D5") (pintype "input"))
      (node (ref "U1") (pin "E3") (pinfunction "GND_E3") (pintype "power_in"))
      (node (ref "U1") (pin "E4") (pinfunction "GND_E4") (pintype "power_in"))
      (node (ref "U1") (pin "E5") (pinfunction "GND_E5") (pintype "power_in"))
      (node (ref "U2") (pin "23") (pinfunction "VSS_23") (pintype "power_in"))
      (node (ref "U2") (pin "35") (pinfunction "VSS_35") (pintype "power_in"))
      (node (ref "U2") (pin "44") (pinfunction "BOOT0_44") (pintype "input"))
      (node (ref "U2") (pin "47") (pinfunction "VSS_47") (pintype "power_in"))
      (node (ref "U2") (pin "49") (pinfunction "EP_49") (pintype "passive"))
      (node (ref "U2") (pin "8") (pinfunction "VSSA/VREF-_8") (pintype "power_in"))
      (node (ref "U3") (pin "2") (pinfunction "GND_2") (pintype "power_in"))
      (node (ref "U3") (pin "4") (pinfunction "TAB_4") (pintype "power_in"))
      (node (ref "U4") (pin "2") (pinfunction "GND_2") (pintype "power_in"))
      (node (ref "U4") (pin "8") (pinfunction "RS_8") (pintype "input"))
      (node (ref "Y1") (pin "2") (pinfunction "GND_2") (pintype "power_in"))
      (node (ref "Y1") (pin "4") (pinfunction "GND_4") (pintype "power_in"))
    )
    (net (code "20") (name "Net-(C12-Pad1)") (class "Default")
      (node (ref "C12") (pin "1") (pinfunction "1_1") (pintype "passive"))
      (node (ref "R5") (pin "2") (pinfunction "2_2") (pintype "passive"))
      (node (ref "Y1") (pin "1") (pinfunction "1_1") (pintype "passive"))
    )
    (net (code "21") (name "Net-(L1-DIN)") (class "Default")
      (node (ref "L1") (pin "4") (pinfunction "DIN_4") (pintype "input"))
      (node (ref "R1") (pin "2") (pinfunction "2_2") (pintype "passive"))
    )
    (net (code "22") (name "Net-(L1-DOUT)") (class "Default")
      (node (ref "L1") (pin "2") (pinfunction "DOUT_2") (pintype "output"))
      (node (ref "L2") (pin "4") (pinfunction "DIN_4") (pintype "input"))
    )
    (net (code "23") (name "Net-(L2-DOUT)") (class "Default")
      (node (ref "L2") (pin "2") (pinfunction "DOUT_2") (pintype "output"))
      (node (ref "L3") (pin "4") (pinfunction "DIN_4") (pintype "input"))
    )
    (net (code "24") (name "Net-(L3-DOUT)") (class "Default")
      (node (ref "L3") (pin "2") (pinfunction "DOUT_2") (pintype "output"))
      (node (ref "L4") (pin "4") (pinfunction "DIN_4") (pintype "input"))
    )
    (net (code "25") (name "Net-(L4-DOUT)") (class "Default")
      (node (ref "L4") (pin "2") (pinfunction "DOUT_2") (pintype "output"))
      (node (ref "L5") (pin "4") (pinfunction "DIN_4") (pintype "input"))
    )
    (net (code "26") (name "Net-(L5-DOUT)") (class "Default")
      (node (ref "L5") (pin "2") (pinfunction "DOUT_2") (pintype "output"))
      (node (ref "L6") (pin "4") (pinfunction "DIN_4") (pintype "input"))
    )
    (net (code "27") (name "Net-(L6-DOUT)") (class "Default")
      (node (ref "L6") (pin "2") (pinfunction "DOUT_2") (pintype "output"))
      (node (ref "L7") (pin "4") (pinfunction "DIN_4") (pintype "input"))
    )
    (net (code "28") (name "Net-(L7-DOUT)") (class "Default")
      (node (ref "L7") (pin "2") (pinfunction "DOUT_2") (pintype "output"))
      (node (ref "L8") (pin "4") (pinfunction "DIN_4") (pintype "input"))
    )
    (net (code "29") (name "Net-(L8-DOUT)") (class "Default")
      (node (ref "L8") (pin "2") (pinfunction "DOUT_2") (pintype "output"))
      (node (ref "L9") (pin "4") (pinfunction "DIN_4") (pintype "input"))
    )
    (net (code "30") (name "Net-(L10-DIN)") (class "Default")
      (node (ref "L10") (pin "4") (pinfunction "DIN_4") (pintype "input"))
      (node (ref "L9") (pin "2") (pinfunction "DOUT_2") (pintype "output"))
    )
    (net (code "31") (name "Net-(L10-DOUT)") (class "Default")
      (node (ref "L10") (pin "2") (pinfunction "DOUT_2") (pintype "output"))
      (node (ref "L11") (pin "4") (pinfunction "DIN_4") (pintype "input"))
    )
    (net (code "32") (name "Net-(L11-DOUT)") (class "Default")
      (node (ref "L11") (pin "2") (pinfunction "DOUT_2") (pintype "output"))
      (node (ref "L12") (pin "4") (pinfunction "DIN_4") (pintype "input"))
    )
    (net (code "33") (name "Net-(L12-DOUT)") (class "Default")
      (node (ref "L12") (pin "2") (pinfunction "DOUT_2") (pintype "output"))
      (node (ref "L13") (pin "4") (pinfunction "DIN_4") (pintype "input"))
    )
    (net (code "34") (name "Net-(L13-DOUT)") (class "Default")
      (node (ref "L13") (pin "2") (pinfunction "DOUT_2") (pintype "output"))
      (node (ref "L14") (pin "4") (pinfunction "DIN_4") (pintype "input"))
    )
    (net (code "35") (name "Net-(L14-DOUT)") (class "Default")
      (node (ref "L14") (pin "2") (pinfunction "DOUT_2") (pintype "output"))
      (node (ref "L15") (pin "4") (pinfunction "DIN_4") (pintype "input"))
    )
    (net (code "36") (name "Net-(L15-DOUT)") (class "Default")
      (node (ref "L15") (pin "2") (pinfunction "DOUT_2") (pintype "output"))
      (node (ref "L16") (pin "4") (pinfunction "DIN_4") (pintype "input"))
    )
    (net (code "37") (name "Net-(L17-DIN)") (class "Default")
      (node (ref "L17") (pin "4") (pinfunction "DIN_4") (pintype "input"))
      (node (ref "R4") (pin "2") (pinfunction "2_2") (pintype "passive"))
    )
    (net (code "38") (name "Net-(L17-DOUT)") (class "Default")
      (node (ref "L17") (pin "2") (pinfunction "DOUT_2") (pintype "output"))
      (node (ref "L18") (pin "4") (pinfunction "DIN_4") (pintype "input"))
    )
    (net (code "39") (name "Net-(L18-DOUT)") (class "Default")
      (node (ref "L18") (pin "2") (pinfunction "DOUT_2") (pintype "output"))
      (node (ref "L19") (pin "4") (pinfunction "DIN_4") (pintype "input"))
    )
    (net (code "40") (name "Net-(L19-DOUT)") (class "Default")
      (node (ref "L19") (pin "2") (pinfunction "DOUT_2") (pintype "output"))
      (node (ref "L20") (pin "4") (pinfunction "DIN_4") (pintype "input"))
    )
    (net (code "41") (name "Net-(U1-FB)") (class "Default")
      (node (ref "R2") (pin "1") (pinfunction "1_1") (pintype "passive"))
      (node (ref "U1") (pin "D1") (pinfunction "FB_D1") (pintype "input"))
    )
    (net (code "42") (name "Net-(U1-RT)") (class "Default")
      (node (ref "R3") (pin "1") (pinfunction "1_1") (pintype "passive"))
      (node (ref "U1") (pin "B5") (pinfunction "RT_B5") (pintype "passive"))
    )
    (net (code "43") (name "Net-(U2-PH0-OSC_IN)") (class "Default")
      (node (ref "C13") (pin "1") (pinfunction "1_1") (pintype "passive"))
      (node (ref "U2") (pin "5") (pinfunction "PH0-OSC_IN_5") (pintype "bidirectional"))
      (node (ref "Y1") (pin "3") (pinfunction "3_3") (pintype "passive"))
    )
    (net (code "44") (name "Net-(U2-PH0-OSC_OUT)") (class "Default")
      (node (ref "R5") (pin "1") (pinfunction "1_1") (pintype "passive"))
      (node (ref "U2") (pin "6") (pinfunction "PH0-OSC_OUT_6") (pintype "bidirectional"))
    )
    (net (code "45") (name "Net-(U2-VCAP_1)") (class "Default")
      (node (ref "C11") (pin "1") (pinfunction "1_1") (pintype "passive"))
      (node (ref "U2") (pin "22") (pinfunction "VCAP_1_22") (pintype "power_in"))
    )
    (net (code "46") (name "unconnected-(J1-PadMP1)") (class "Default")
      (node (ref "J1") (pin "MP1") (pinfunction "MP1_MP1") (pintype "passive"))
    )
    (net (code "47") (name "unconnected-(J1-PadMP2)") (class "Default")
      (node (ref "J1") (pin "MP2") (pinfunction "MP2_MP2") (pintype "passive"))
    )
    (net (code "48") (name "unconnected-(J2-PadMP1)") (class "Default")
      (node (ref "J2") (pin "MP1") (pinfunction "MP1_MP1") (pintype "passive"))
    )
    (net (code "49") (name "unconnected-(J2-PadMP2)") (class "Default")
      (node (ref "J2") (pin "MP2") (pinfunction "MP2_MP2") (pintype "passive"))
    )
    (net (code "50") (name "unconnected-(J3-PadMP1)") (class "Default")
      (node (ref "J3") (pin "MP1") (pinfunction "MP1_MP1") (pintype "passive"))
    )
    (net (code "51") (name "unconnected-(J3-PadMP2)") (class "Default")
      (node (ref "J3") (pin "MP2") (pinfunction "MP2_MP2") (pintype "passive"))
    )
    (net (code "52") (name "unconnected-(J4-PadMP1)") (class "Default")
      (node (ref "J4") (pin "MP1") (pinfunction "MP1_MP1") (pintype "passive"))
    )
    (net (code "53") (name "unconnected-(J4-PadMP2)") (class "Default")
      (node (ref "J4") (pin "MP2") (pinfunction "MP2_MP2") (pintype "passive"))
    )
    (net (code "54") (name "unconnected-(J5-PadMP1)") (class "Default")
      (node (ref "J5") (pin "MP1") (pinfunction "MP1_MP1") (pintype "passive"))
    )
    (net (code "55") (name "unconnected-(J5-PadMP2)") (class "Default")
      (node (ref "J5") (pin "MP2") (pinfunction "MP2_MP2") (pintype "passive"))
    )
    (net (code "56") (name "unconnected-(J6-PadMP1)") (class "Default")
      (node (ref "J6") (pin "MP1") (pinfunction "MP1_MP1") (pintype "passive"))
    )
    (net (code "57") (name "unconnected-(J6-PadMP2)") (class "Default")
      (node (ref "J6") (pin "MP2") (pinfunction "MP2_MP2") (pintype "passive"))
    )
    (net (code "58") (name "unconnected-(J8-~{RESET}-Pad3)") (class "Default")
      (node (ref "J8") (pin "3") (pinfunction "~{RESET}_3") (pintype "input+no_connect"))
    )
    (net (code "59") (name "unconnected-(L16-DOUT-Pad2)") (class "Default")
      (node (ref "L16") (pin "2") (pinfunction "DOUT_2") (pintype "output"))
    )
    (net (code "60") (name "unconnected-(L20-DOUT-Pad2)") (class "Default")
      (node (ref "L20") (pin "2") (pinfunction "DOUT_2") (pintype "output"))
    )
    (net (code "61") (name "unconnected-(U1-PG-PadB1)") (class "Default")
      (node (ref "U1") (pin "B1") (pinfunction "PG_B1") (pintype "output"))
    )
    (net (code "62") (name "unconnected-(U1-TR{slash}SS-PadC1)") (class "Default")
      (node (ref "U1") (pin "C1") (pinfunction "TR/SS_C1") (pintype "bidirectional"))
    )
    (net (code "63") (name "unconnected-(U2-PA0-Pad10)") (class "Default")
      (node (ref "U2") (pin "10") (pinfunction "PA0_10") (pintype "bidirectional"))
    )
    (net (code "64") (name "unconnected-(U2-PA1-Pad11)") (class "Default")
      (node (ref "U2") (pin "11") (pinfunction "PA1_11") (pintype "bidirectional"))
    )
    (net (code "65") (name "unconnected-(U2-PA2-Pad12)") (class "Default")
      (node (ref "U2") (pin "12") (pinfunction "PA2_12") (pintype "bidirectional"))
    )
    (net (code "66") (name "unconnected-(U2-PA3-Pad13)") (class "Default")
      (node (ref "U2") (pin "13") (pinfunction "PA3_13") (pintype "bidirectional"))
    )
    (net (code "67") (name "unconnected-(U2-PA4-Pad14)") (class "Default")
      (node (ref "U2") (pin "14") (pinfunction "PA4_14") (pintype "bidirectional"))
    )
    (net (code "68") (name "unconnected-(U2-PA5-Pad15)") (class "Default")
      (node (ref "U2") (pin "15") (pinfunction "PA5_15") (pintype "bidirectional"))
    )
    (net (code "69") (name "unconnected-(U2-PA6-Pad16)") (class "Default")
      (node (ref "U2") (pin "16") (pinfunction "PA6_16") (pintype "bidirectional"))
    )
    (net (code "70") (name "unconnected-(U2-PA8-Pad29)") (class "Default")
      (node (ref "U2") (pin "29") (pinfunction "PA8_29") (pintype "bidirectional"))
    )
    (net (code "71") (name "unconnected-(U2-PA9-Pad30)") (class "Default")
      (node (ref "U2") (pin "30") (pinfunction "PA9_30") (pintype "bidirectional"))
    )
    (net (code "72") (name "unconnected-(U2-PA10-Pad31)") (class "Default")
      (node (ref "U2") (pin "31") (pinfunction "PA10_31") (pintype "bidirectional"))
    )
    (net (code "73") (name "unconnected-(U2-PA15-Pad38)") (class "Default")
      (node (ref "U2") (pin "38") (pinfunction "PA15_38") (pintype "bidirectional"))
    )
    (net (code "74") (name "unconnected-(U2-PB2-Pad20)") (class "Default")
      (node (ref "U2") (pin "20") (pinfunction "PB2_20") (pintype "bidirectional"))
    )
    (net (code "75") (name "unconnected-(U2-PB4-Pad40)") (class "Default")
      (node (ref "U2") (pin "40") (pinfunction "PB4_40") (pintype "bidirectional"))
    )
    (net (code "76") (name "unconnected-(U2-PB9-Pad46)") (class "Default")
      (node (ref "U2") (pin "46") (pinfunction "PB9_46") (pintype "bidirectional"))
    )
    (net (code "77") (name "unconnected-(U2-PB10-Pad21)") (class "Default")
      (node (ref "U2") (pin "21") (pinfunction "PB10_21") (pintype "bidirectional"))
    )
    (net (code "78") (name "unconnected-(U2-PB12-Pad25)") (class "Default")
      (node (ref "U2") (pin "25") (pinfunction "PB12_25") (pintype "bidirectional"))
    )
    (net (code "79") (name "unconnected-(U2-PB13-Pad26)") (class "Default")
      (node (ref "U2") (pin "26") (pinfunction "PB13_26") (pintype "bidirectional"))
    )
    (net (code "80") (name "unconnected-(U2-PB14-Pad27)") (class "Default")
      (node (ref "U2") (pin "27") (pinfunction "PB14_27") (pintype "bidirectional"))
    )
    (net (code "81") (name "unconnected-(U2-PC13-Pad2)") (class "Default")
      (node (ref "U2") (pin "2") (pinfunction "PC13_2") (pintype "bidirectional"))
    )
    (net (code "82") (name "unconnected-(U2-PC14-OSC32_IN-Pad3)") (class "Default")
      (node (ref "U2") (pin "3") (pinfunction "PC14-OSC32_IN_3") (pintype "bidirectional"))
    )
    (net (code "83") (name "unconnected-(U2-PC15-OSC32_OUT-Pad4)") (class "Default")
      (node (ref "U2") (pin "4") (pinfunction "PC15-OSC32_OUT_4") (pintype "bidirectional"))
    )
    (net (code "84") (name "unconnected-(U4-VREF-Pad5)") (class "Default")
      (node (ref "U4") (pin "5") (pinfunction "VREF_5") (pintype "output"))
    )
  )
)
